# RscDroneBadge.net
KiCad netlist of a schematic drawn in EAGLE
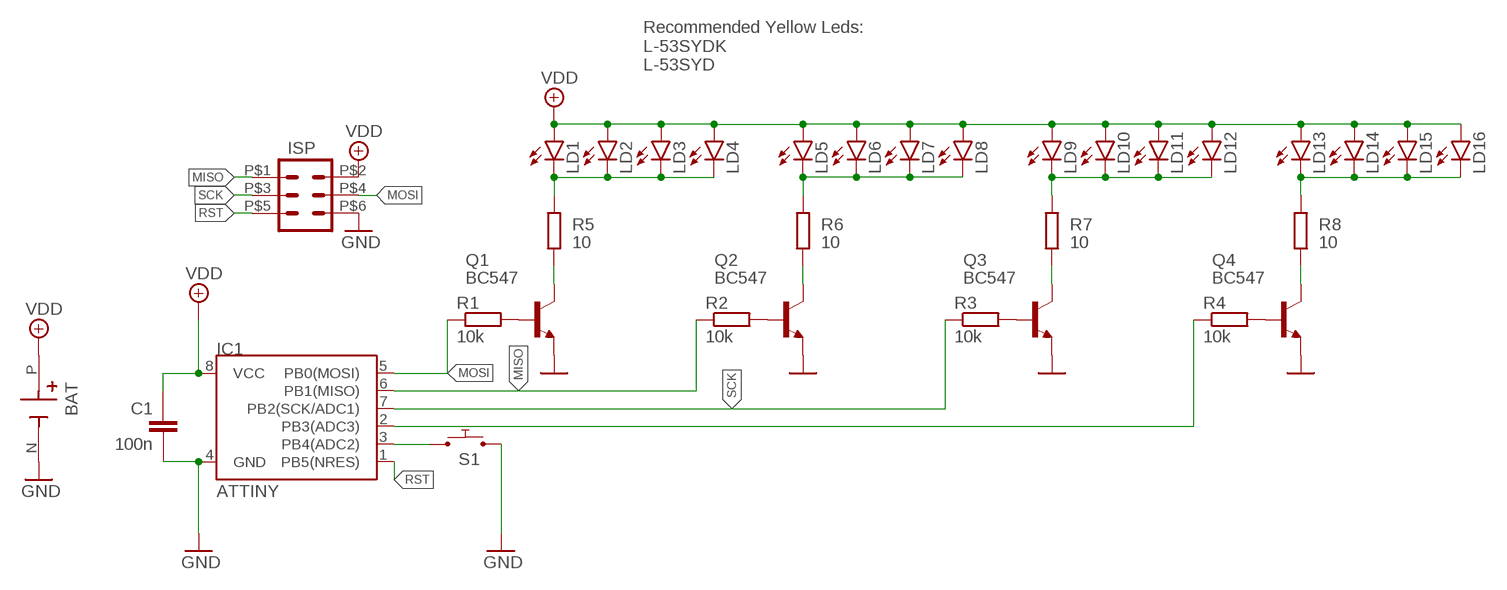
[diagram p0: schematic, sheet 1]

(export (version "E")
  (design (tool "Eeschema 10.0.6"))
  (components
    (comp (ref "BAT")
      (value "CR2032 HOLDER")
      (footprint "eagle-import:CR2032_PLASTIC")
      (libsource (lib "eagle-import") (part "CR2032_PLASTIC"))
    )
    (comp (ref "C1")
      (value "100n")
      (footprint "eagle-import:C_2.54")
      (libsource (lib "eagle-import") (part "CAPACITOR_THT_2.54"))
    )
    (comp (ref "IC1")
      (value "ATTINY")
      (footprint "eagle-import:DIL08")
      (libsource (lib "eagle-import") (part "ATTINY85-20PU"))
    )
    (comp (ref "ISP")
      (value "2X3POGONO_VIA")
      (footprint "eagle-import:2X3_POGO_NO_VIA")
      (libsource (lib "eagle-import") (part "2X3POGONO_VIA"))
    )
    (comp (ref "LD1")
      (value "LED_THT-5MM_NICE")
      (footprint "eagle-import:LED_5MM_NICE")
      (libsource (lib "eagle-import") (part "LED_THT-5MM_NICE"))
    )
    (comp (ref "LD2")
      (value "LED_THT-5MM_NICE")
      (footprint "eagle-import:LED_5MM_NICE")
      (libsource (lib "eagle-import") (part "LED_THT-5MM_NICE"))
    )
    (comp (ref "LD3")
      (value "LED_THT-5MM_NICE")
      (footprint "eagle-import:LED_5MM_NICE")
      (libsource (lib "eagle-import") (part "LED_THT-5MM_NICE"))
    )
    (comp (ref "LD4")
      (value "LED_THT-5MM_NICE")
      (footprint "eagle-import:LED_5MM_NICE")
      (libsource (lib "eagle-import") (part "LED_THT-5MM_NICE"))
    )
    (comp (ref "LD5")
      (value "LED_THT-5MM_NICE")
      (footprint "eagle-import:LED_5MM_NICE")
      (libsource (lib "eagle-import") (part "LED_THT-5MM_NICE"))
    )
    (comp (ref "LD6")
      (value "LED_THT-5MM_NICE")
      (footprint "eagle-import:LED_5MM_NICE")
      (libsource (lib "eagle-import") (part "LED_THT-5MM_NICE"))
    )
    (comp (ref "LD7")
      (value "LED_THT-5MM_NICE")
      (footprint "eagle-import:LED_5MM_NICE")
      (libsource (lib "eagle-import") (part "LED_THT-5MM_NICE"))
    )
    (comp (ref "LD8")
      (value "LED_THT-5MM_NICE")
      (footprint "eagle-import:LED_5MM_NICE")
      (libsource (lib "eagle-import") (part "LED_THT-5MM_NICE"))
    )
    (comp (ref "LD9")
      (value "LED_THT-5MM_NICE")
      (footprint "eagle-import:LED_5MM_NICE")
      (libsource (lib "eagle-import") (part "LED_THT-5MM_NICE"))
    )
    (comp (ref "LD10")
      (value "LED_THT-5MM_NICE")
      (footprint "eagle-import:LED_5MM_NICE")
      (libsource (lib "eagle-import") (part "LED_THT-5MM_NICE"))
    )
    (comp (ref "LD11")
      (value "LED_THT-5MM_NICE")
      (footprint "eagle-import:LED_5MM_NICE")
      (libsource (lib "eagle-import") (part "LED_THT-5MM_NICE"))
    )
    (comp (ref "LD12")
      (value "LED_THT-5MM_NICE")
      (footprint "eagle-import:LED_5MM_NICE")
      (libsource (lib "eagle-import") (part "LED_THT-5MM_NICE"))
    )
    (comp (ref "LD13")
      (value "LED_THT-5MM_NICE")
      (footprint "eagle-import:LED_5MM_NICE")
      (libsource (lib "eagle-import") (part "LED_THT-5MM_NICE"))
    )
    (comp (ref "LD14")
      (value "LED_THT-5MM_NICE")
      (footprint "eagle-import:LED_5MM_NICE")
      (libsource (lib "eagle-import") (part "LED_THT-5MM_NICE"))
    )
    (comp (ref "LD15")
      (value "LED_THT-5MM_NICE")
      (footprint "eagle-import:LED_5MM_NICE")
      (libsource (lib "eagle-import") (part "LED_THT-5MM_NICE"))
    )
    (comp (ref "LD16")
      (value "LED_THT-5MM_NICE")
      (footprint "eagle-import:LED_5MM_NICE")
      (libsource (lib "eagle-import") (part "LED_THT-5MM_NICE"))
    )
    (comp (ref "Q1")
      (value "BC547")
      (footprint "eagle-import:TO92_ROUND")
      (libsource (lib "eagle-import") (part "BC547"))
    )
    (comp (ref "Q2")
      (value "BC547")
      (footprint "eagle-import:TO92_ROUND")
      (libsource (lib "eagle-import") (part "BC547"))
    )
    (comp (ref "Q3")
      (value "BC547")
      (footprint "eagle-import:TO92_ROUND")
      (libsource (lib "eagle-import") (part "BC547"))
    )
    (comp (ref "Q4")
      (value "BC547")
      (footprint "eagle-import:TO92_ROUND")
      (libsource (lib "eagle-import") (part "BC547"))
    )
    (comp (ref "R1")
      (value "10k")
      (footprint "eagle-import:RCL_0207")
      (libsource (lib "eagle-import") (part "RESISTOR_0207_THT0204/7_ROUND"))
    )
    (comp (ref "R2")
      (value "10k")
      (footprint "eagle-import:RCL_0207")
      (libsource (lib "eagle-import") (part "RESISTOR_0207_THT0204/7_ROUND"))
    )
    (comp (ref "R3")
      (value "10k")
      (footprint "eagle-import:RCL_0207")
      (libsource (lib "eagle-import") (part "RESISTOR_0207_THT0204/7_ROUND"))
    )
    (comp (ref "R4")
      (value "10k")
      (footprint "eagle-import:RCL_0207")
      (libsource (lib "eagle-import") (part "RESISTOR_0207_THT0204/7_ROUND"))
    )
    (comp (ref "R5")
      (value "10")
      (footprint "eagle-import:RCL_0207")
      (libsource (lib "eagle-import") (part "RESISTOR_0207_THT0204/7_ROUND"))
    )
    (comp (ref "R6")
      (value "10")
      (footprint "eagle-import:RCL_0207")
      (libsource (lib "eagle-import") (part "RESISTOR_0207_THT0204/7_ROUND"))
    )
    (comp (ref "R7")
      (value "10")
      (footprint "eagle-import:RCL_0207")
      (libsource (lib "eagle-import") (part "RESISTOR_0207_THT0204/7_ROUND"))
    )
    (comp (ref "R8")
      (value "10")
      (footprint "eagle-import:RCL_0207")
      (libsource (lib "eagle-import") (part "RESISTOR_0207_THT0204/7_ROUND"))
    )
    (comp (ref "S1")
      (value "6x6mm BUTTON")
      (footprint "eagle-import:TACTILE-PTH")
      (libsource (lib "eagle-import") (part "PUSH_MOMENTARY_THT_6X6MM"))
    )
  )
  (nets
    (net (code "1") (name "GND") (class "Default")
      (node (ref "BAT") (pin "N") (pinfunction "NEG_N") (pintype "passive"))
      (node (ref "C1") (pin "2") (pinfunction "2_2") (pintype "passive"))
      (node (ref "IC1") (pin "4") (pinfunction "GND_4") (pintype "bidirectional"))
      (node (ref "ISP") (pin "P$6") (pinfunction "6_P$6") (pintype "passive"))
      (node (ref "Q1") (pin "1") (pinfunction "E_1") (pintype "passive"))
      (node (ref "Q2") (pin "1") (pinfunction "E_1") (pintype "passive"))
      (node (ref "Q3") (pin "1") (pinfunction "E_1") (pintype "passive"))
      (node (ref "Q4") (pin "1") (pinfunction "E_1") (pintype "passive"))
      (node (ref "S1") (pin "3") (pinfunction "2_3") (pintype "passive"))
      (node (ref "S1") (pin "4") (pinfunction "2_4") (pintype "passive"))
    )
    (net (code "2") (name "MISO") (class "Default")
      (node (ref "IC1") (pin "6") (pinfunction "PB1(MISO)_6") (pintype "bidirectional"))
      (node (ref "ISP") (pin "P$1") (pinfunction "1_P$1") (pintype "passive"))
      (node (ref "R2") (pin "1") (pinfunction "1_1") (pintype "passive"))
    )
    (net (code "3") (name "MOSI") (class "Default")
      (node (ref "IC1") (pin "5") (pinfunction "PB0(MOSI)_5") (pintype "bidirectional"))
      (node (ref "ISP") (pin "P$4") (pinfunction "4_P$4") (pintype "passive"))
      (node (ref "R1") (pin "1") (pinfunction "1_1") (pintype "passive"))
    )
    (net (code "4") (name "Net-(IC1-PB3(ADC3))") (class "Default")
      (node (ref "IC1") (pin "2") (pinfunction "PB3(ADC3)_2") (pintype "bidirectional"))
      (node (ref "R4") (pin "1") (pinfunction "1_1") (pintype "passive"))
    )
    (net (code "5") (name "Net-(IC1-PB4(ADC2))") (class "Default")
      (node (ref "IC1") (pin "3") (pinfunction "PB4(ADC2)_3") (pintype "bidirectional"))
      (node (ref "S1") (pin "1") (pinfunction "1_1") (pintype "passive"))
      (node (ref "S1") (pin "2") (pinfunction "1_2") (pintype "passive"))
    )
    (net (code "6") (name "Net-(LD1-C)") (class "Default")
      (node (ref "LD1") (pin "K") (pinfunction "C_K") (pintype "passive"))
      (node (ref "LD2") (pin "K") (pinfunction "C_K") (pintype "passive"))
      (node (ref "LD3") (pin "K") (pinfunction "C_K") (pintype "passive"))
      (node (ref "LD4") (pin "K") (pinfunction "C_K") (pintype "passive"))
      (node (ref "R5") (pin "2") (pinfunction "2_2") (pintype "passive"))
    )
    (net (code "7") (name "Net-(LD5-C)") (class "Default")
      (node (ref "LD5") (pin "K") (pinfunction "C_K") (pintype "passive"))
      (node (ref "LD6") (pin "K") (pinfunction "C_K") (pintype "passive"))
      (node (ref "LD7") (pin "K") (pinfunction "C_K") (pintype "passive"))
      (node (ref "LD8") (pin "K") (pinfunction "C_K") (pintype "passive"))
      (node (ref "R6") (pin "2") (pinfunction "2_2") (pintype "passive"))
    )
    (net (code "8") (name "Net-(LD10-C)") (class "Default")
      (node (ref "LD10") (pin "K") (pinfunction "C_K") (pintype "passive"))
      (node (ref "LD11") (pin "K") (pinfunction "C_K") (pintype "passive"))
      (node (ref "LD12") (pin "K") (pinfunction "C_K") (pintype "passive"))
      (node (ref "LD9") (pin "K") (pinfunction "C_K") (pintype "passive"))
      (node (ref "R7") (pin "2") (pinfunction "2_2") (pintype "passive"))
    )
    (net (code "9") (name "Net-(LD13-C)") (class "Default")
      (node (ref "LD13") (pin "K") (pinfunction "C_K") (pintype "passive"))
      (node (ref "LD14") (pin "K") (pinfunction "C_K") (pintype "passive"))
      (node (ref "LD15") (pin "K") (pinfunction "C_K") (pintype "passive"))
      (node (ref "LD16") (pin "K") (pinfunction "C_K") (pintype "passive"))
      (node (ref "R8") (pin "2") (pinfunction "2_2") (pintype "passive"))
    )
    (net (code "10") (name "Net-(Q1-B)") (class "Default")
      (node (ref "Q1") (pin "2") (pinfunction "B_2") (pintype "passive"))
      (node (ref "R1") (pin "2") (pinfunction "2_2") (pintype "passive"))
    )
    (net (code "11") (name "Net-(Q1-C)") (class "Default")
      (node (ref "Q1") (pin "3") (pinfunction "C_3") (pintype "passive"))
      (node (ref "R5") (pin "1") (pinfunction "1_1") (pintype "passive"))
    )
    (net (code "12") (name "Net-(Q2-B)") (class "Default")
      (node (ref "Q2") (pin "2") (pinfunction "B_2") (pintype "passive"))
      (node (ref "R2") (pin "2") (pinfunction "2_2") (pintype "passive"))
    )
    (net (code "13") (name "Net-(Q2-C)") (class "Default")
      (node (ref "Q2") (pin "3") (pinfunction "C_3") (pintype "passive"))
      (node (ref "R6") (pin "1") (pinfunction "1_1") (pintype "passive"))
    )
    (net (code "14") (name "Net-(Q3-B)") (class "Default")
      (node (ref "Q3") (pin "2") (pinfunction "B_2") (pintype "passive"))
      (node (ref "R3") (pin "2") (pinfunction "2_2") (pintype "passive"))
    )
    (net (code "15") (name "Net-(Q3-C)") (class "Default")
      (node (ref "Q3") (pin "3") (pinfunction "C_3") (pintype "passive"))
      (node (ref "R7") (pin "1") (pinfunction "1_1") (pintype "passive"))
    )
    (net (code "16") (name "Net-(Q4-B)") (class "Default")
      (node (ref "Q4") (pin "2") (pinfunction "B_2") (pintype "passive"))
      (node (ref "R4") (pin "2") (pinfunction "2_2") (pintype "passive"))
    )
    (net (code "17") (name "Net-(Q4-C)") (class "Default")
      (node (ref "Q4") (pin "3") (pinfunction "C_3") (pintype "passive"))
      (node (ref "R8") (pin "1") (pinfunction "1_1") (pintype "passive"))
    )
    (net (code "18") (name "RST") (class "Default")
      (node (ref "IC1") (pin "1") (pinfunction "PB5(NRES)_1") (pintype "bidirectional"))
      (node (ref "ISP") (pin "P$5") (pinfunction "5_P$5") (pintype "passive"))
    )
    (net (code "19") (name "SCK") (class "Default")
      (node (ref "IC1") (pin "7") (pinfunction "PB2(SCK/ADC1)_7") (pintype "bidirectional"))
      (node (ref "ISP") (pin "P$3") (pinfunction "3_P$3") (pintype "passive"))
      (node (ref "R3") (pin "1") (pinfunction "1_1") (pintype "passive"))
    )
    (net (code "20") (name "VDD") (class "Default")
      (node (ref "BAT") (pin "P") (pinfunction "POS_P") (pintype "passive"))
      (node (ref "C1") (pin "1") (pinfunction "1_1") (pintype "passive"))
      (node (ref "IC1") (pin "8") (pinfunction "VCC_8") (pintype "bidirectional"))
      (node (ref "ISP") (pin "P$2") (pinfunction "2_P$2") (pintype "passive"))
      (node (ref "LD1") (pin "A") (pinfunction "A_A") (pintype "passive"))
      (node (ref "LD10") (pin "A") (pinfunction "A_A") (pintype "passive"))
      (node (ref "LD11") (pin "A") (pinfunction "A_A") (pintype "passive"))
      (node (ref "LD12") (pin "A") (pinfunction "A_A") (pintype "passive"))
      (node (ref "LD13") (pin "A") (pinfunction "A_A") (pintype "passive"))
      (node (ref "LD14") (pin "A") (pinfunction "A_A") (pintype "passive"))
      (node (ref "LD15") (pin "A") (pinfunction "A_A") (pintype "passive"))
      (node (ref "LD16") (pin "A") (pinfunction "A_A") (pintype "passive"))
      (node (ref "LD2") (pin "A") (pinfunction "A_A") (pintype "passive"))
      (node (ref "LD3") (pin "A") (pinfunction "A_A") (pintype "passive"))
      (node (ref "LD4") (pin "A") (pinfunction "A_A") (pintype "passive"))
      (node (ref "LD5") (pin "A") (pinfunction "A_A") (pintype "passive"))
      (node (ref "LD6") (pin "A") (pinfunction "A_A") (pintype "passive"))
      (node (ref "LD7") (pin "A") (pinfunction "A_A") (pintype "passive"))
      (node (ref "LD8") (pin "A") (pinfunction "A_A") (pintype "passive"))
      (node (ref "LD9") (pin "A") (pinfunction "A_A") (pintype "passive"))
    )
  )
)
